# SRAM0_-_IS61WV12816DBLL-10BLI.net
KiCad netlist of a schematic drawn in Altium Designer
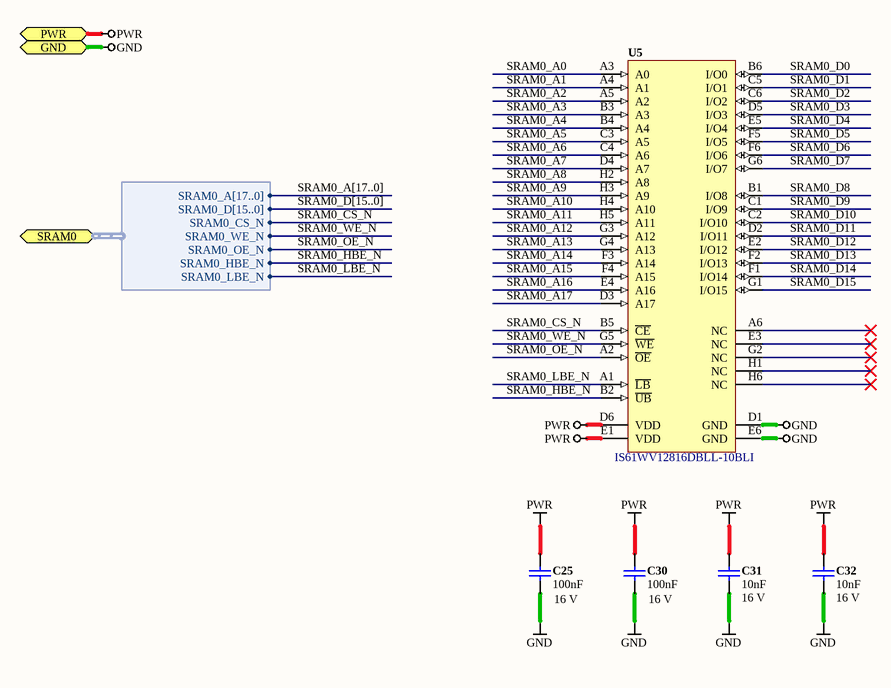
[diagram p0: SRAM0 - IS61WV12816DBLL-10BLI.SchDoc]

(export (version "E")
  (design (tool "Eeschema 10.0.6"))
  (components
    (comp (ref "C25")
      (value "100nF")
      (footprint "CAPC0402(1005)60_L")
      (fields
        (field (name "RATED VOLTAGE") "16 V")
        (field (name "TOLERANCE") "±10%")
        (field (name "MANUFACTURER PART NUMBER") "C0402C104K8PACTU")
        (field (name "Comment") "CAP 100nF 16V 0402(1005)")
      )
      (libsource (lib "Component_Database") (part "CAP_NP"))
    )
    (comp (ref "C30")
      (value "100nF")
      (footprint "CAPC0402(1005)60_L")
      (fields
        (field (name "RATED VOLTAGE") "16 V")
        (field (name "TOLERANCE") "±10%")
        (field (name "MANUFACTURER PART NUMBER") "C0402C104K8PACTU")
        (field (name "Comment") "CAP 100nF 16V 0402(1005)")
      )
      (libsource (lib "Component_Database") (part "CAP_NP"))
    )
    (comp (ref "C31")
      (value "10nF")
      (footprint "CAPC0402(1005)33_L")
      (description "CAP 10nF 16V ±10% 0402 (1005 Metric) Thickness 0.33mm SMD")
      (fields
        (field (name "TOLERANCE") "±10%")
        (field (name "RATED VOLTAGE") "16 V")
        (field (name "MANUFACTURER PART NUMBER") "GRM155R61C103KA01D")
      )
      (libsource (lib "Altium Content Vault") (part "CMP-1034-01875-1"))
    )
    (comp (ref "C32")
      (value "10nF")
      (footprint "CAPC0402(1005)33_L")
      (description "CAP 10nF 16V ±10% 0402 (1005 Metric) Thickness 0.33mm SMD")
      (fields
        (field (name "TOLERANCE") "±10%")
        (field (name "RATED VOLTAGE") "16 V")
        (field (name "MANUFACTURER PART NUMBER") "GRM155R61C103KA01D")
      )
      (libsource (lib "Altium Content Vault") (part "CMP-1034-01875-1"))
    )
    (comp (ref "U5")
      (value "IS61WV12816DBLL-10BLI")
      (footprint "ISSI-TF-BGA-48-6000X8000DE")
      (description "2 M High Speed Asynchronous CMOS SRAM, 128 K x 16, -40 to 85 degC, 48-Pin BGA (TF-BGA-48), Pb-Free")
      (fields (field (name "MANUFACTURER") "Integrated Silicon Solution Inc (ISSI)"))
      (libsource (lib "Altium Content Vault") (part "ISSI-IS61WV12816DALL_DBLL-TF-BGA-48"))
    )
  )
  (nets
    (net (code "2") (name "/SRAM0_A0") (class "Default")
      (node (ref "U5") (pin "A3") (pinfunction "A0_A3") (pintype "input"))
    )
    (net (code "3") (name "/SRAM0_A1") (class "Default")
      (node (ref "U5") (pin "A4") (pinfunction "A1_A4") (pintype "input"))
    )
    (net (code "4") (name "/SRAM0_A2") (class "Default")
      (node (ref "U5") (pin "A5") (pinfunction "A2_A5") (pintype "input"))
    )
    (net (code "5") (name "/SRAM0_A3") (class "Default")
      (node (ref "U5") (pin "B3") (pinfunction "A3_B3") (pintype "input"))
    )
    (net (code "6") (name "/SRAM0_A4") (class "Default")
      (node (ref "U5") (pin "B4") (pinfunction "A4_B4") (pintype "input"))
    )
    (net (code "7") (name "/SRAM0_A5") (class "Default")
      (node (ref "U5") (pin "C3") (pinfunction "A5_C3") (pintype "input"))
    )
    (net (code "8") (name "/SRAM0_A6") (class "Default")
      (node (ref "U5") (pin "C4") (pinfunction "A6_C4") (pintype "input"))
    )
    (net (code "9") (name "/SRAM0_A7") (class "Default")
      (node (ref "U5") (pin "D4") (pinfunction "A7_D4") (pintype "input"))
    )
    (net (code "10") (name "/SRAM0_A8") (class "Default")
      (node (ref "U5") (pin "H2") (pinfunction "A8_H2") (pintype "input"))
    )
    (net (code "11") (name "/SRAM0_A9") (class "Default")
      (node (ref "U5") (pin "H3") (pinfunction "A9_H3") (pintype "input"))
    )
    (net (code "12") (name "/SRAM0_A10") (class "Default")
      (node (ref "U5") (pin "H4") (pinfunction "A10_H4") (pintype "input"))
    )
    (net (code "13") (name "/SRAM0_A11") (class "Default")
      (node (ref "U5") (pin "H5") (pinfunction "A11_H5") (pintype "input"))
    )
    (net (code "14") (name "/SRAM0_A12") (class "Default")
      (node (ref "U5") (pin "G3") (pinfunction "A12_G3") (pintype "input"))
    )
    (net (code "15") (name "/SRAM0_A13") (class "Default")
      (node (ref "U5") (pin "G4") (pinfunction "A13_G4") (pintype "input"))
    )
    (net (code "16") (name "/SRAM0_A14") (class "Default")
      (node (ref "U5") (pin "F3") (pinfunction "A14_F3") (pintype "input"))
    )
    (net (code "17") (name "/SRAM0_A15") (class "Default")
      (node (ref "U5") (pin "F4") (pinfunction "A15_F4") (pintype "input"))
    )
    (net (code "18") (name "/SRAM0_A16") (class "Default")
      (node (ref "U5") (pin "E4") (pinfunction "A16_E4") (pintype "input"))
    )
    (net (code "19") (name "/SRAM0_A17") (class "Default")
      (node (ref "U5") (pin "D3") (pinfunction "A17_D3") (pintype "input"))
    )
    (net (code "21") (name "/SRAM0_CS_N") (class "Default")
      (node (ref "U5") (pin "B5") (pinfunction "~{CE}_B5") (pintype "input"))
    )
    (net (code "22") (name "/SRAM0_D0") (class "Default")
      (node (ref "U5") (pin "B6") (pinfunction "I/O0_B6") (pintype "bidirectional"))
    )
    (net (code "23") (name "/SRAM0_D1") (class "Default")
      (node (ref "U5") (pin "C5") (pinfunction "I/O1_C5") (pintype "bidirectional"))
    )
    (net (code "24") (name "/SRAM0_D2") (class "Default")
      (node (ref "U5") (pin "C6") (pinfunction "I/O2_C6") (pintype "bidirectional"))
    )
    (net (code "25") (name "/SRAM0_D3") (class "Default")
      (node (ref "U5") (pin "D5") (pinfunction "I/O3_D5") (pintype "bidirectional"))
    )
    (net (code "26") (name "/SRAM0_D4") (class "Default")
      (node (ref "U5") (pin "E5") (pinfunction "I/O4_E5") (pintype "bidirectional"))
    )
    (net (code "27") (name "/SRAM0_D5") (class "Default")
      (node (ref "U5") (pin "F5") (pinfunction "I/O5_F5") (pintype "bidirectional"))
    )
    (net (code "28") (name "/SRAM0_D6") (class "Default")
      (node (ref "U5") (pin "F6") (pinfunction "I/O6_F6") (pintype "bidirectional"))
    )
    (net (code "29") (name "/SRAM0_D7") (class "Default")
      (node (ref "U5") (pin "G6") (pinfunction "I/O7_G6") (pintype "bidirectional"))
    )
    (net (code "30") (name "/SRAM0_D8") (class "Default")
      (node (ref "U5") (pin "B1") (pinfunction "I/O8_B1") (pintype "bidirectional"))
    )
    (net (code "31") (name "/SRAM0_D9") (class "Default")
      (node (ref "U5") (pin "C1") (pinfunction "I/O9_C1") (pintype "bidirectional"))
    )
    (net (code "32") (name "/SRAM0_D10") (class "Default")
      (node (ref "U5") (pin "C2") (pinfunction "I/O10_C2") (pintype "bidirectional"))
    )
    (net (code "33") (name "/SRAM0_D11") (class "Default")
      (node (ref "U5") (pin "D2") (pinfunction "I/O11_D2") (pintype "bidirectional"))
    )
    (net (code "34") (name "/SRAM0_D12") (class "Default")
      (node (ref "U5") (pin "E2") (pinfunction "I/O12_E2") (pintype "bidirectional"))
    )
    (net (code "35") (name "/SRAM0_D13") (class "Default")
      (node (ref "U5") (pin "F2") (pinfunction "I/O13_F2") (pintype "bidirectional"))
    )
    (net (code "36") (name "/SRAM0_D14") (class "Default")
      (node (ref "U5") (pin "F1") (pinfunction "I/O14_F1") (pintype "bidirectional"))
    )
    (net (code "37") (name "/SRAM0_D15") (class "Default")
      (node (ref "U5") (pin "G1") (pinfunction "I/O15_G1") (pintype "bidirectional"))
    )
    (net (code "39") (name "/SRAM0_HBE_N") (class "Default")
      (node (ref "U5") (pin "B2") (pinfunction "~{UB}_B2") (pintype "input"))
    )
    (net (code "40") (name "/SRAM0_LBE_N") (class "Default")
      (node (ref "U5") (pin "A1") (pinfunction "~{LB}_A1") (pintype "input"))
    )
    (net (code "41") (name "/SRAM0_OE_N") (class "Default")
      (node (ref "U5") (pin "A2") (pinfunction "~{OE}_A2") (pintype "input"))
    )
    (net (code "42") (name "/SRAM0_WE_N") (class "Default")
      (node (ref "U5") (pin "G5") (pinfunction "~{WE}_G5") (pintype "input"))
    )
    (net (code "44") (name "GND") (class "Default")
      (node (ref "C25") (pin "2") (pinfunction "2_2") (pintype "passive"))
      (node (ref "C30") (pin "2") (pinfunction "2_2") (pintype "passive"))
      (node (ref "C31") (pin "2") (pinfunction "2_2") (pintype "passive"))
      (node (ref "C32") (pin "2") (pinfunction "2_2") (pintype "passive"))
      (node (ref "U5") (pin "D1") (pinfunction "GND_D1") (pintype "power_in"))
      (node (ref "U5") (pin "E6") (pinfunction "GND_E6") (pintype "power_in"))
    )
    (net (code "45") (name "PWR") (class "Default")
      (node (ref "C25") (pin "1") (pinfunction "1_1") (pintype "passive"))
      (node (ref "C30") (pin "1") (pinfunction "1_1") (pintype "passive"))
      (node (ref "C31") (pin "1") (pinfunction "1_1") (pintype "passive"))
      (node (ref "C32") (pin "1") (pinfunction "1_1") (pintype "passive"))
      (node (ref "U5") (pin "D6") (pinfunction "VDD_D6") (pintype "power_in"))
      (node (ref "U5") (pin "E1") (pinfunction "VDD_E1") (pintype "power_in"))
    )
    (net (code "46") (name "unconnected-(U5-NC-PadA6)") (class "Default")
      (node (ref "U5") (pin "A6") (pinfunction "NC_A6") (pintype "passive+no_connect"))
    )
    (net (code "47") (name "unconnected-(U5-NC-PadE3)") (class "Default")
      (node (ref "U5") (pin "E3") (pinfunction "NC_E3") (pintype "passive+no_connect"))
    )
    (net (code "48") (name "unconnected-(U5-NC-PadG2)") (class "Default")
      (node (ref "U5") (pin "G2") (pinfunction "NC_G2") (pintype "passive+no_connect"))
    )
    (net (code "49") (name "unconnected-(U5-NC-PadH1)") (class "Default")
      (node (ref "U5") (pin "H1") (pinfunction "NC_H1") (pintype "passive+no_connect"))
    )
    (net (code "50") (name "unconnected-(U5-NC-PadH6)") (class "Default")
      (node (ref "U5") (pin "H6") (pinfunction "NC_H6") (pintype "passive+no_connect"))
    )
  )
)
